# LT1054_Bipolar5V.net
KiCad netlist of a schematic drawn in EAGLE
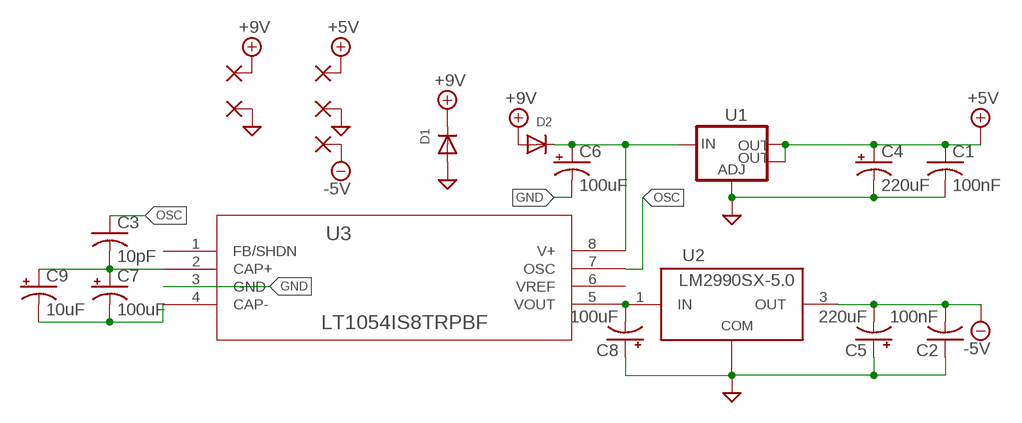
[diagram p0: schematic, sheet 1]

(export (version "E")
  (design (tool "Eeschema 10.0.6"))
  (components
    (comp (ref "C1")
      (value "100nF")
      (footprint "eagle-import:C0603")
      (libsource (lib "eagle-import") (part "C-USC0603"))
    )
    (comp (ref "C2")
      (value "100nF")
      (footprint "eagle-import:C0603")
      (libsource (lib "eagle-import") (part "C-USC0603"))
    )
    (comp (ref "C3")
      (value "10pF")
      (footprint "eagle-import:C0603")
      (libsource (lib "eagle-import") (part "C-USC0603"))
    )
    (comp (ref "C4")
      (value "220uF")
      (footprint "eagle-import:PANASONIC_E")
      (libsource (lib "eagle-import") (part "CPOL-USE"))
    )
    (comp (ref "C5")
      (value "220uF")
      (footprint "eagle-import:PANASONIC_E")
      (libsource (lib "eagle-import") (part "CPOL-USE"))
    )
    (comp (ref "C6")
      (value "100uF")
      (footprint "eagle-import:PANASONIC_D")
      (libsource (lib "eagle-import") (part "CPOL-USD"))
    )
    (comp (ref "C7")
      (value "100uF")
      (footprint "eagle-import:PANASONIC_D")
      (libsource (lib "eagle-import") (part "CPOL-USD"))
    )
    (comp (ref "C8")
      (value "100uF")
      (footprint "eagle-import:PANASONIC_D")
      (libsource (lib "eagle-import") (part "CPOL-USD"))
    )
    (comp (ref "C9")
      (value "10uF")
      (footprint "eagle-import:PANASONIC_B")
      (libsource (lib "eagle-import") (part "CPOL-USB"))
    )
    (comp (ref "D1")
      (value "DIODESOD-123")
      (footprint "eagle-import:SOD-123")
      (libsource (lib "eagle-import") (part "DIODESOD-123"))
    )
    (comp (ref "D2")
      (value "DIODESOD-123")
      (footprint "eagle-import:SOD-123")
      (libsource (lib "eagle-import") (part "DIODESOD-123"))
    )
    (comp (ref "PAD1")
      (value "SMD2")
      (footprint "eagle-import:SMD1,27-2,54")
      (libsource (lib "eagle-import") (part "SMD2"))
    )
    (comp (ref "PAD2")
      (value "1,6/0,8")
      (footprint "eagle-import:1,6_0,8")
      (libsource (lib "eagle-import") (part "1,6/0,8"))
    )
    (comp (ref "PAD3")
      (value "1,6/0,8")
      (footprint "eagle-import:1,6_0,8")
      (libsource (lib "eagle-import") (part "1,6/0,8"))
    )
    (comp (ref "PAD4")
      (value "1,6/0,8")
      (footprint "eagle-import:1,6_0,8")
      (libsource (lib "eagle-import") (part "1,6/0,8"))
    )
    (comp (ref "PAD5")
      (value "1,6/0,8")
      (footprint "eagle-import:1,6_0,8")
      (libsource (lib "eagle-import") (part "1,6/0,8"))
    )
    (comp (ref "U1")
      (value "V_REG_LM1117SOT223")
      (footprint "eagle-import:SOT223")
      (libsource (lib "eagle-import") (part "V_REG_LM1117SOT223"))
    )
    (comp (ref "U2")
      (value "LM2990SX-5.0")
      (footprint "eagle-import:D2PAK-3")
      (fields
        (field (name "DIGIKEY_PART_NUMBER") "296-20796-2-ND")
        (field (name "MANUFACTURER") "Texas Instruments")
        (field (name "MPN") "UA7805CKTTR")
        (field (name "CREATED_BY") "PCBLayout.com")
      )
      (libsource (lib "eagle-import") (part "UA7805CKTTR"))
    )
    (comp (ref "U3")
      (value "LT1054IS8TRPBF")
      (footprint "eagle-import:SO-8_S")
      (fields (field (name "MF") "Analog Devices") (field (name "MP") "LT1054IS8#TRPBF"))
      (libsource (lib "eagle-import") (part "LT1054IS8TRPBF"))
    )
  )
  (nets
    (net (code "1") (name "+5V") (class "Default")
      (node (ref "C1") (pin "1") (pinfunction "1_1") (pintype "passive"))
      (node (ref "C4") (pin "+") (pinfunction "+_+") (pintype "passive"))
      (node (ref "PAD3") (pin "1") (pinfunction "P_1") (pintype "passive"))
      (node (ref "U1") (pin "2") (pinfunction "OUT_2") (pintype "output"))
      (node (ref "U1") (pin "4") (pinfunction "OUT_4") (pintype "output"))
    )
    (net (code "2") (name "+9V") (class "Default")
      (node (ref "D1") (pin "C") (pinfunction "C_C") (pintype "passive"))
      (node (ref "D2") (pin "A") (pinfunction "A_A") (pintype "passive"))
      (node (ref "PAD1") (pin "1") (pinfunction "P_1") (pintype "passive"))
    )
    (net (code "3") (name "-5V") (class "Default")
      (node (ref "C2") (pin "2") (pinfunction "2_2") (pintype "passive"))
      (node (ref "C5") (pin "-") (pinfunction "-_-") (pintype "passive"))
      (node (ref "PAD5") (pin "1") (pinfunction "P_1") (pintype "passive"))
      (node (ref "U2") (pin "3") (pinfunction "OUT_3") (pintype "output"))
    )
    (net (code "4") (name "/VREF") (class "Default")
      (node (ref "U3") (pin "6") (pinfunction "VREF_6") (pintype "power_in"))
    )
    (net (code "5") (name "GND") (class "Default")
      (node (ref "C1") (pin "2") (pinfunction "2_2") (pintype "passive"))
      (node (ref "C2") (pin "1") (pinfunction "1_1") (pintype "passive"))
      (node (ref "C4") (pin "-") (pinfunction "-_-") (pintype "passive"))
      (node (ref "C5") (pin "+") (pinfunction "+_+") (pintype "passive"))
      (node (ref "C6") (pin "-") (pinfunction "-_-") (pintype "passive"))
      (node (ref "C8") (pin "+") (pinfunction "+_+") (pintype "passive"))
      (node (ref "D1") (pin "A") (pinfunction "A_A") (pintype "passive"))
      (node (ref "PAD2") (pin "1") (pinfunction "P_1") (pintype "passive"))
      (node (ref "PAD4") (pin "1") (pinfunction "P_1") (pintype "passive"))
      (node (ref "U1") (pin "1") (pinfunction "ADJ_1") (pintype "input"))
      (node (ref "U2") (pin "2") (pinfunction "COM_2") (pintype "power_in"))
      (node (ref "U2") (pin "4") (pinfunction "COM_4") (pintype "power_in"))
      (node (ref "U3") (pin "3") (pinfunction "GND_3") (pintype "power_in"))
    )
    (net (code "6") (name "Net-(U1-IN)") (class "Default")
      (node (ref "C6") (pin "+") (pinfunction "+_+") (pintype "passive"))
      (node (ref "D2") (pin "C") (pinfunction "C_C") (pintype "passive"))
      (node (ref "U1") (pin "3") (pinfunction "IN_3") (pintype "input"))
      (node (ref "U3") (pin "8") (pinfunction "V+_8") (pintype "power_in"))
    )
    (net (code "7") (name "Net-(U2-IN)") (class "Default")
      (node (ref "C8") (pin "-") (pinfunction "-_-") (pintype "passive"))
      (node (ref "U2") (pin "1") (pinfunction "IN_1") (pintype "input"))
      (node (ref "U3") (pin "5") (pinfunction "VOUT_5") (pintype "output"))
    )
    (net (code "8") (name "Net-(U3-CAP+)") (class "Default")
      (node (ref "C3") (pin "2") (pinfunction "2_2") (pintype "passive"))
      (node (ref "C7") (pin "+") (pinfunction "+_+") (pintype "passive"))
      (node (ref "C9") (pin "+") (pinfunction "+_+") (pintype "passive"))
      (node (ref "U3") (pin "2") (pinfunction "CAP+_2") (pintype "passive"))
    )
    (net (code "9") (name "Net-(U3-CAP-)") (class "Default")
      (node (ref "C7") (pin "-") (pinfunction "-_-") (pintype "passive"))
      (node (ref "C9") (pin "-") (pinfunction "-_-") (pintype "passive"))
      (node (ref "U3") (pin "4") (pinfunction "CAP-_4") (pintype "passive"))
    )
    (net (code "10") (name "OSC") (class "Default")
      (node (ref "C3") (pin "1") (pinfunction "1_1") (pintype "passive"))
      (node (ref "U3") (pin "7") (pinfunction "OSC_7") (pintype "passive"))
    )
    (net (code "11") (name "unconnected-(U3-FB{slash}SHDN-Pad1)") (class "Default")
      (node (ref "U3") (pin "1") (pinfunction "FB/SHDN_1") (pintype "passive"))
    )
  )
)
